# 16-ESP32S3.net
KiCad netlist of a schematic drawn in Altium Designer
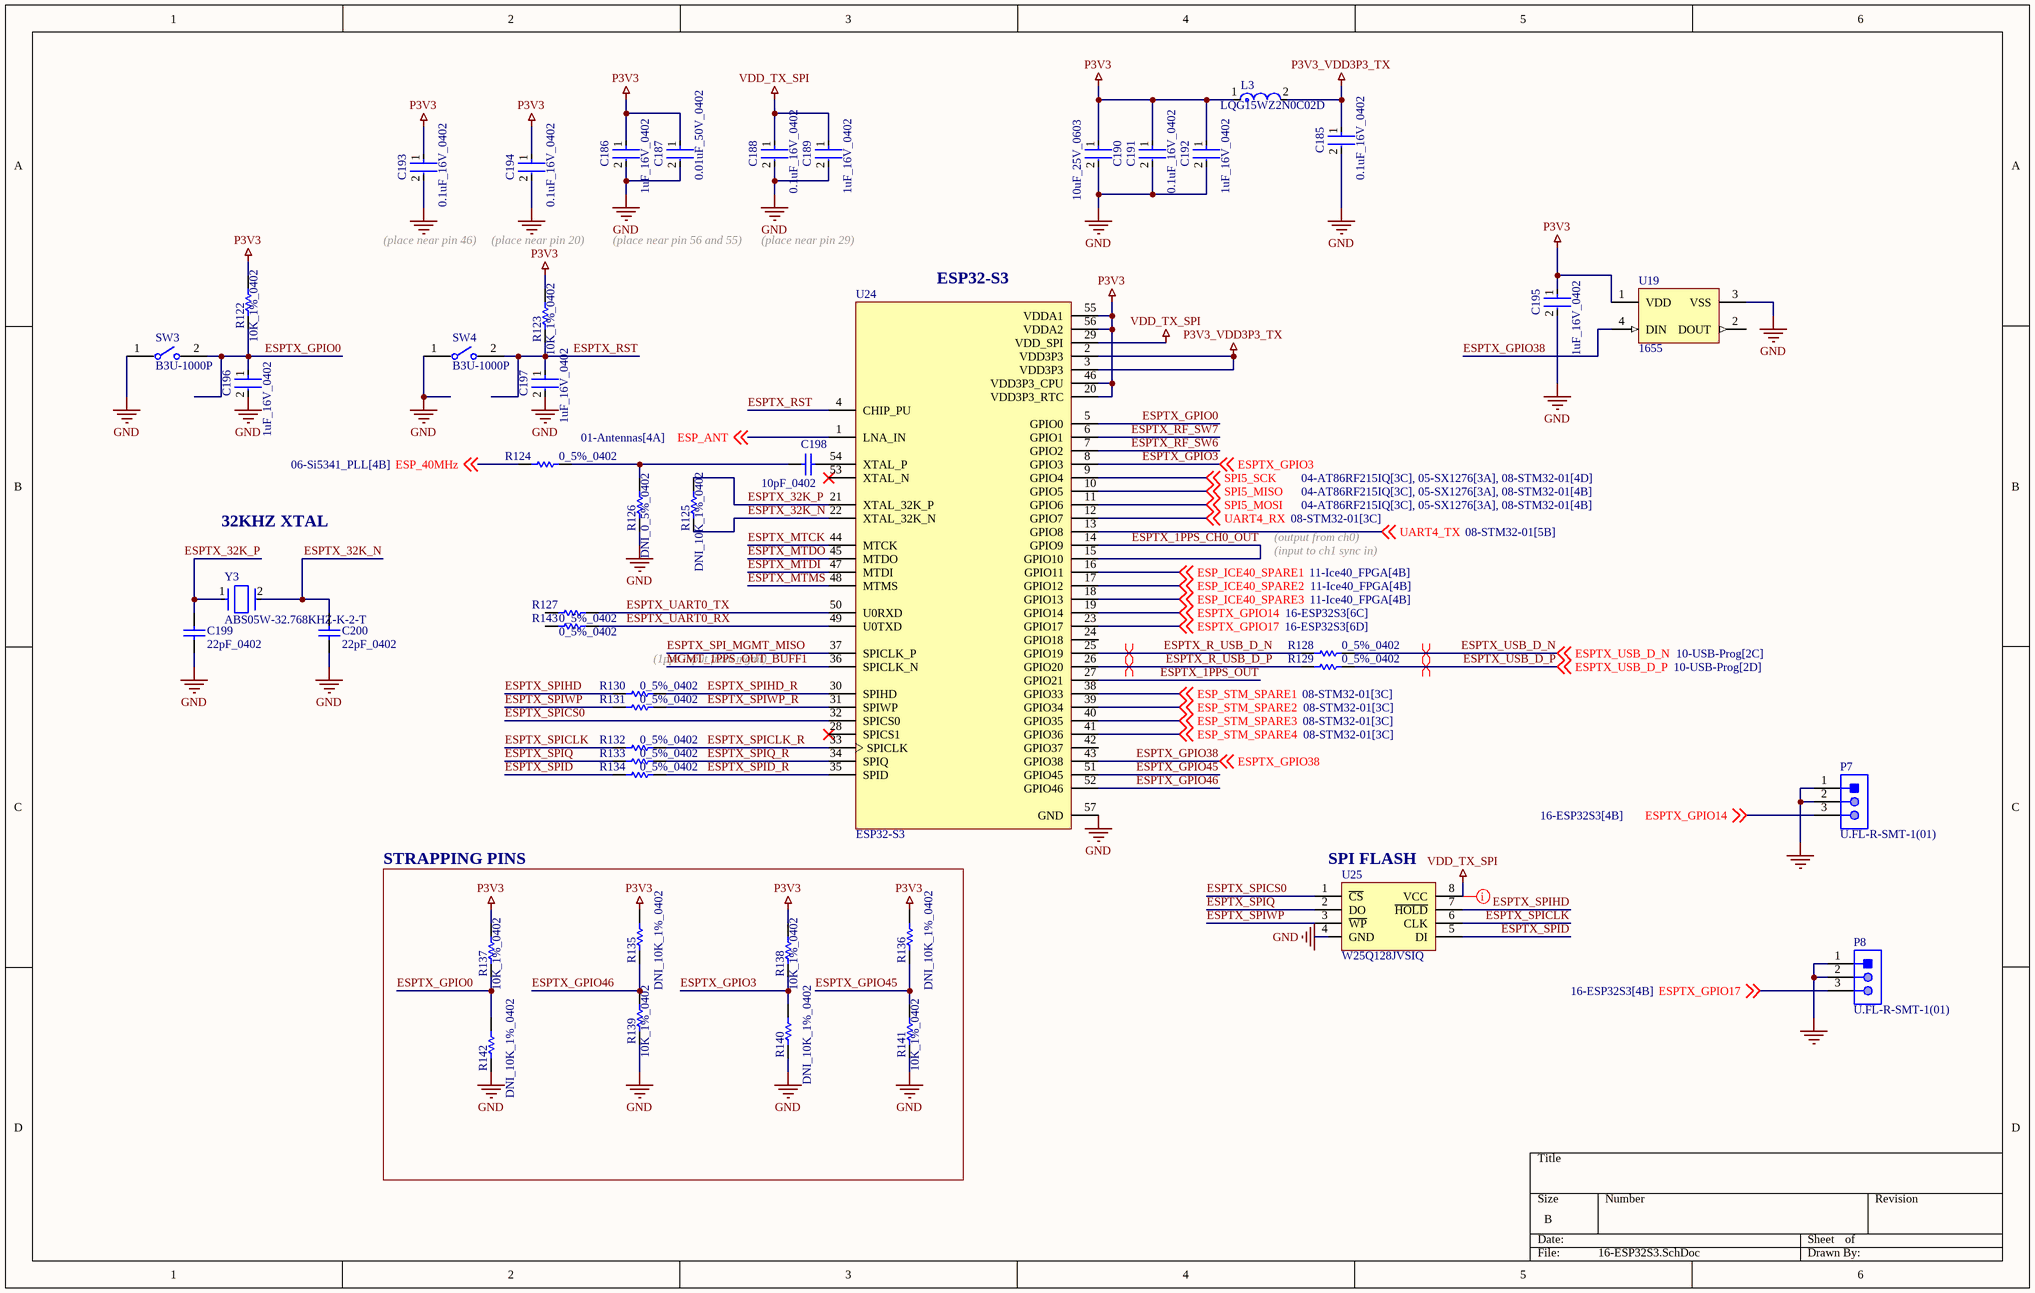
[diagram p0: 16-ESP32S3.SchDoc]

(export (version "E")
  (design (tool "Eeschema 10.0.6"))
  (components
    (comp (ref "C185")
      (value "0.1uF_16V_0402")
      (footprint "FP-C0402-BB-MFG")
      (description "CAP CER 0.1UF 16V 5% X7R 0402")
      (fields
        (field (name "MANUFACTURER") "Kemet")
        (field (name "MANUFACTURER PART NUMBER") "C0402C104J4RACTU")
      )
      (libsource (lib "Altium Content Vault") (part "b4654b650e69147ec39a6b967a45e02"))
    )
    (comp (ref "C186")
      (value "1uF_16V_0402")
      (footprint "FP-0402-L_1_0_0_05-W_0_5-IPC_A")
      (description "None")
      (fields (field (name "TOLERANCE") "10%"))
      (libsource (lib "Altium Content Vault") (part "b4654b650e69147ec39a6b967a45e02"))
    )
    (comp (ref "C187")
      (value "0.01uF_50V_0402")
      (footprint "FP-GCM155-0_05-IPC_C")
      (description "Ceramic Capacitor for Automotive 10nF ±10% 50VDC X7R 0402 Paper T/R")
      (fields (field (name "TOLERANCE") "10%") (field (name "VOLTAGE") "50V"))
      (libsource (lib "Altium Content Vault") (part "02cd4be3c70576c341d710602a673aa"))
    )
    (comp (ref "C188")
      (value "0.1uF_16V_0402")
      (footprint "FP-C0402-BB-MFG")
      (description "CAP CER 0.1UF 16V 5% X7R 0402")
      (fields
        (field (name "MANUFACTURER") "Kemet")
        (field (name "MANUFACTURER PART NUMBER") "C0402C104J4RACTU")
      )
      (libsource (lib "Altium Content Vault") (part "b4654b650e69147ec39a6b967a45e02"))
    )
    (comp (ref "C189")
      (value "1uF_16V_0402")
      (footprint "FP-0402-L_1_0_0_05-W_0_5-IPC_A")
      (description "None")
      (fields (field (name "TOLERANCE") "10%"))
      (libsource (lib "Altium Content Vault") (part "b4654b650e69147ec39a6b967a45e02"))
    )
    (comp (ref "C190")
      (value "10uF_25V_0603")
      (footprint "FP-CL10-IPC_C")
      (description "Cap Ceramic 10uF 25V X5R ±20% Pad SMD 0603 +85°C T/R")
      (fields (field (name "TOLERANCE") "20%"))
      (libsource (lib "Altium Content Vault") (part "b4654b650e69147ec39a6b967a45e02"))
    )
    (comp (ref "C191")
      (value "0.1uF_16V_0402")
      (footprint "FP-C0402-BB-MFG")
      (description "CAP CER 0.1UF 16V 5% X7R 0402")
      (fields
        (field (name "MANUFACTURER") "Kemet")
        (field (name "MANUFACTURER PART NUMBER") "C0402C104J4RACTU")
      )
      (libsource (lib "Altium Content Vault") (part "b4654b650e69147ec39a6b967a45e02"))
    )
    (comp (ref "C192")
      (value "1uF_16V_0402")
      (footprint "FP-0402-L_1_0_0_05-W_0_5-IPC_A")
      (description "None")
      (fields (field (name "TOLERANCE") "10%"))
      (libsource (lib "Altium Content Vault") (part "b4654b650e69147ec39a6b967a45e02"))
    )
    (comp (ref "C193")
      (value "0.1uF_16V_0402")
      (footprint "FP-C0402-BB-MFG")
      (description "CAP CER 0.1UF 16V 5% X7R 0402")
      (fields
        (field (name "MANUFACTURER") "Kemet")
        (field (name "MANUFACTURER PART NUMBER") "C0402C104J4RACTU")
      )
      (libsource (lib "Altium Content Vault") (part "b4654b650e69147ec39a6b967a45e02"))
    )
    (comp (ref "C194")
      (value "0.1uF_16V_0402")
      (footprint "FP-C0402-BB-MFG")
      (description "CAP CER 0.1UF 16V 5% X7R 0402")
      (fields
        (field (name "MANUFACTURER") "Kemet")
        (field (name "MANUFACTURER PART NUMBER") "C0402C104J4RACTU")
      )
      (libsource (lib "Altium Content Vault") (part "b4654b650e69147ec39a6b967a45e02"))
    )
    (comp (ref "C195")
      (value "1uF_16V_0402")
      (footprint "FP-0402-L_1_0_0_05-W_0_5-IPC_A")
      (description "None")
      (fields (field (name "TOLERANCE") "10%"))
      (libsource (lib "Altium Content Vault") (part "b4654b650e69147ec39a6b967a45e02"))
    )
    (comp (ref "C196")
      (value "1uF_16V_0402")
      (footprint "FP-0402-L_1_0_0_05-W_0_5-IPC_A")
      (description "None")
      (fields (field (name "TOLERANCE") "10%"))
      (libsource (lib "Altium Content Vault") (part "b4654b650e69147ec39a6b967a45e02"))
    )
    (comp (ref "C197")
      (value "1uF_16V_0402")
      (footprint "FP-0402-L_1_0_0_05-W_0_5-IPC_A")
      (description "None")
      (fields (field (name "TOLERANCE") "10%"))
      (libsource (lib "Altium Content Vault") (part "b4654b650e69147ec39a6b967a45e02"))
    )
    (comp (ref "C198")
      (value "10pF_0402")
      (footprint "CAPC1005X55X25ML05T05")
      (description "Chip Capacitor, 10 pF, +/- 5%, 50 V, -55 to 125 degC, 0402 (1005 Metric), RoHS, Tape and Reel")
      (fields (field (name "TOLERANCE") "5%") (field (name "MANUFACTURER") "Yageo"))
      (libsource (lib "Altium Content Vault") (part "CAP-NP-2"))
    )
    (comp (ref "C199")
      (value "22pF_0402")
      (footprint "CAPC1005X55X25ML05T05")
      (description "Chip Capacitor, 22 pF, +/- 5%, 50 V, -55 to 125 degC, 0402 (1005 Metric), RoHS, Tape and Reel")
      (fields (field (name "MANUFACTURER") "Yageo") (field (name "TOLERANCE") "5%"))
      (libsource (lib "Altium Content Vault") (part "CAP-NP-2"))
    )
    (comp (ref "C200")
      (value "22pF_0402")
      (footprint "CAPC1005X55X25ML05T05")
      (description "Chip Capacitor, 22 pF, +/- 5%, 50 V, -55 to 125 degC, 0402 (1005 Metric), RoHS, Tape and Reel")
      (fields (field (name "MANUFACTURER") "Yageo") (field (name "TOLERANCE") "5%"))
      (libsource (lib "Altium Content Vault") (part "CAP-NP-2"))
    )
    (comp (ref "L3")
      (value "LQG15WZ2N0C02D")
      (footprint "FP-LQG15WH_02-IPC_B")
      (description "Multilayer type Inductor for Automotive 2nH ±0.2nH 0.05Ω 1000mA 0402")
      (libsource (lib "Altium Content Vault") (part "4cc4b267dca4c8e51f7102f422741d8"))
    )
    (comp (ref "P7")
      (value "U.FL-R-SMT-1(01)")
      (footprint "HRS-U.FL-R-SMT-3_V")
      (description "Ultra Small Coaxial Connector, 6 GHz, -40 to 90 degC, 3-Pin SMD, RoHS, Bulk")
      (fields (field (name "MANUFACTURER") "Hirose Electric"))
      (libsource (lib "Altium Content Vault") (part "CN-1P-M-R3"))
    )
    (comp (ref "P8")
      (value "U.FL-R-SMT-1(01)")
      (footprint "HRS-U.FL-R-SMT-3_V")
      (description "Ultra Small Coaxial Connector, 6 GHz, -40 to 90 degC, 3-Pin SMD, RoHS, Bulk")
      (fields (field (name "MANUFACTURER") "Hirose Electric"))
      (libsource (lib "Altium Content Vault") (part "CN-1P-M-R3"))
    )
    (comp (ref "R122")
      (value "10K_1%_0402")
      (footprint "RESC1005X40X25NL10T10")
      (fields (field (name "MANUFACTURER") "Bourns") (field (name "PART NUMBER") "CR0402-FX-1002GLF"))
      (libsource (lib "Altium Content Vault") (part "RES"))
    )
    (comp (ref "R123")
      (value "10K_1%_0402")
      (footprint "RESC1005X40X25NL10T10")
      (fields (field (name "MANUFACTURER") "Bourns") (field (name "PART NUMBER") "CR0402-FX-1002GLF"))
      (libsource (lib "Altium Content Vault") (part "RES"))
    )
    (comp (ref "R124")
      (value "0_5%_0402")
      (footprint "RESC1005X40X25NL05T10")
      (fields (field (name "MANUFACTURER") "Panasonic") (field (name "PART NUMBER") "ERJ-U020R00X"))
      (libsource (lib "Altium Content Vault") (part "RES"))
    )
    (comp (ref "R125")
      (value "DNI_10K_1%_0402")
      (footprint "RESC1005X40X25NL10T10")
      (fields (field (name "MANUFACTURER") "Bourns") (field (name "PART NUMBER") "CR0402-FX-1002GLF"))
      (libsource (lib "Altium Content Vault") (part "RES"))
    )
    (comp (ref "R126")
      (value "DNI_0_5%_0402")
      (footprint "RESC1005X40X25NL05T10")
      (fields (field (name "MANUFACTURER") "Panasonic") (field (name "PART NUMBER") "ERJ-U020R00X"))
      (libsource (lib "Altium Content Vault") (part "RES"))
    )
    (comp (ref "R127")
      (value "0_5%_0402")
      (footprint "RESC1005X40X25NL05T10")
      (fields (field (name "MANUFACTURER") "Panasonic") (field (name "PART NUMBER") "ERJ-U020R00X"))
      (libsource (lib "Altium Content Vault") (part "RES"))
    )
    (comp (ref "R128")
      (value "0_5%_0402")
      (footprint "RESC1005X40X25NL05T10")
      (fields (field (name "MANUFACTURER") "Panasonic") (field (name "PART NUMBER") "ERJ-U020R00X"))
      (libsource (lib "Altium Content Vault") (part "RES"))
    )
    (comp (ref "R129")
      (value "0_5%_0402")
      (footprint "RESC1005X40X25NL05T10")
      (fields (field (name "MANUFACTURER") "Panasonic") (field (name "PART NUMBER") "ERJ-U020R00X"))
      (libsource (lib "Altium Content Vault") (part "RES"))
    )
    (comp (ref "R130")
      (value "0_5%_0402")
      (footprint "RESC1005X40X25NL05T10")
      (fields (field (name "MANUFACTURER") "Panasonic") (field (name "PART NUMBER") "ERJ-U020R00X"))
      (libsource (lib "Altium Content Vault") (part "RES"))
    )
    (comp (ref "R131")
      (value "0_5%_0402")
      (footprint "RESC1005X40X25NL05T10")
      (fields (field (name "MANUFACTURER") "Panasonic") (field (name "PART NUMBER") "ERJ-U020R00X"))
      (libsource (lib "Altium Content Vault") (part "RES"))
    )
    (comp (ref "R132")
      (value "0_5%_0402")
      (footprint "RESC1005X40X25NL05T10")
      (fields (field (name "MANUFACTURER") "Panasonic") (field (name "PART NUMBER") "ERJ-U020R00X"))
      (libsource (lib "Altium Content Vault") (part "RES"))
    )
    (comp (ref "R133")
      (value "0_5%_0402")
      (footprint "RESC1005X40X25NL05T10")
      (fields (field (name "MANUFACTURER") "Panasonic") (field (name "PART NUMBER") "ERJ-U020R00X"))
      (libsource (lib "Altium Content Vault") (part "RES"))
    )
    (comp (ref "R134")
      (value "0_5%_0402")
      (footprint "RESC1005X40X25NL05T10")
      (fields (field (name "MANUFACTURER") "Panasonic") (field (name "PART NUMBER") "ERJ-U020R00X"))
      (libsource (lib "Altium Content Vault") (part "RES"))
    )
    (comp (ref "R135")
      (value "DNI_10K_1%_0402")
      (footprint "RESC1005X40X25NL10T10")
      (fields (field (name "MANUFACTURER") "Bourns") (field (name "PART NUMBER") "CR0402-FX-1002GLF"))
      (libsource (lib "Altium Content Vault") (part "RES"))
    )
    (comp (ref "R136")
      (value "DNI_10K_1%_0402")
      (footprint "RESC1005X40X25NL10T10")
      (fields (field (name "MANUFACTURER") "Bourns") (field (name "PART NUMBER") "CR0402-FX-1002GLF"))
      (libsource (lib "Altium Content Vault") (part "RES"))
    )
    (comp (ref "R137")
      (value "10K_1%_0402")
      (footprint "RESC1005X40X25NL10T10")
      (fields (field (name "MANUFACTURER") "Bourns") (field (name "PART NUMBER") "CR0402-FX-1002GLF"))
      (libsource (lib "Altium Content Vault") (part "RES"))
    )
    (comp (ref "R138")
      (value "10K_1%_0402")
      (footprint "RESC1005X40X25NL10T10")
      (fields (field (name "MANUFACTURER") "Bourns") (field (name "PART NUMBER") "CR0402-FX-1002GLF"))
      (libsource (lib "Altium Content Vault") (part "RES"))
    )
    (comp (ref "R139")
      (value "10K_1%_0402")
      (footprint "RESC1005X40X25NL10T10")
      (fields (field (name "MANUFACTURER") "Bourns") (field (name "PART NUMBER") "CR0402-FX-1002GLF"))
      (libsource (lib "Altium Content Vault") (part "RES"))
    )
    (comp (ref "R140")
      (value "DNI_10K_1%_0402")
      (footprint "RESC1005X40X25NL10T10")
      (fields (field (name "MANUFACTURER") "Bourns") (field (name "PART NUMBER") "CR0402-FX-1002GLF"))
      (libsource (lib "Altium Content Vault") (part "RES"))
    )
    (comp (ref "R141")
      (value "10K_1%_0402")
      (footprint "RESC1005X40X25NL10T10")
      (fields (field (name "MANUFACTURER") "Bourns") (field (name "PART NUMBER") "CR0402-FX-1002GLF"))
      (libsource (lib "Altium Content Vault") (part "RES"))
    )
    (comp (ref "R142")
      (value "DNI_10K_1%_0402")
      (footprint "RESC1005X40X25NL10T10")
      (fields (field (name "MANUFACTURER") "Bourns") (field (name "PART NUMBER") "CR0402-FX-1002GLF"))
      (libsource (lib "Altium Content Vault") (part "RES"))
    )
    (comp (ref "R143")
      (value "0_5%_0402")
      (footprint "RESC1005X40X25NL05T10")
      (fields (field (name "MANUFACTURER") "Panasonic") (field (name "PART NUMBER") "ERJ-U020R00X"))
      (libsource (lib "Altium Content Vault") (part "RES"))
    )
    (comp (ref "SW3")
      (value "B3U-1000P")
      (footprint "FP-B3U-1000P-MFG")
      (description "SWITCH TACTILE SPST-NO 0.05A 12V")
      (libsource (lib "Altium Content Vault") (part "ae622034201233ca1abcedc05908f33"))
    )
    (comp (ref "SW4")
      (value "B3U-1000P")
      (footprint "FP-B3U-1000P-MFG")
      (description "SWITCH TACTILE SPST-NO 0.05A 12V")
      (libsource (lib "Altium Content Vault") (part "ae622034201233ca1abcedc05908f33"))
    )
    (comp (ref "U19")
      (value "1655")
      (footprint "ADA-RGB-1655_V")
      (fields (field (name "MANUFACTURER") "Adafruit-Industries-LLC"))
      (libsource (lib "Altium Content Vault") (part "ADA-RGB-1655-4"))
    )
    (comp (ref "U24")
      (value "ESP32-S3")
      (footprint "IC_ESP32-S3")
      (fields (field (name "MF") "Espressif Systems"))
      (libsource (lib "LotusSound") (part "IC_ESP32-S3"))
    )
    (comp (ref "U25")
      (value "W25Q128JVSIQ")
      (footprint "IC_W25Q128JVSIQ")
      (description "NOR Flash Serial (SPI, Dual SPI, Quad SPI) 3.3V 128M-bit 16M x 8 6ns 8-Pin SOIC Tube")
      (fields (field (name "MANUFACTURER") "Winbond"))
      (libsource (lib "LotusSound") (part "IC_W25Q128JVSIQ"))
    )
    (comp (ref "Y3")
      (value "ABS05W-32.768KHZ-K-2-T")
      (footprint "FP-ABS05W-MFG")
      (description "Crystal 32.768kHz ±20ppm (Tol) 4pF 85kΩ 2-Pin SMD T/R")
      (libsource (lib "Altium Content Vault") (part "c23a69dc6c9e2f18f2079038eb95dd1"))
    )
  )
  (nets
    (net (code "1") (name "/ESPTX_1PPS_CH0_OUT") (class "Default")
      (node (ref "U24") (pin "14") (pinfunction "GPIO9_14") (pintype "passive"))
      (node (ref "U24") (pin "15") (pinfunction "GPIO10_15") (pintype "passive"))
    )
    (net (code "2") (name "/ESPTX_1PPS_OUT") (class "Default")
      (node (ref "U24") (pin "27") (pinfunction "GPIO21_27") (pintype "passive"))
    )
    (net (code "3") (name "/ESPTX_32K_N") (class "Default")
      (node (ref "C200") (pin "2") (pinfunction "2_2") (pintype "passive"))
      (node (ref "R125") (pin "1") (pinfunction "1_1") (pintype "passive"))
      (node (ref "U24") (pin "22") (pinfunction "XTAL_32K_N_22") (pintype "passive"))
      (node (ref "Y3") (pin "2") (pinfunction "2_2") (pintype "passive"))
    )
    (net (code "4") (name "/ESPTX_32K_P") (class "Default")
      (node (ref "C199") (pin "2") (pinfunction "2_2") (pintype "passive"))
      (node (ref "R125") (pin "2") (pinfunction "2_2") (pintype "passive"))
      (node (ref "U24") (pin "21") (pinfunction "XTAL_32K_P_21") (pintype "passive"))
      (node (ref "Y3") (pin "1") (pinfunction "1_1") (pintype "passive"))
    )
    (net (code "5") (name "/ESPTX_GPIO0") (class "Default")
      (node (ref "C196") (pin "1") (pinfunction "1_1") (pintype "passive"))
      (node (ref "R122") (pin "1") (pinfunction "1_1") (pintype "passive"))
      (node (ref "R137") (pin "1") (pinfunction "1_1") (pintype "passive"))
      (node (ref "R142") (pin "2") (pinfunction "2_2") (pintype "passive"))
      (node (ref "SW3") (pin "2") (pinfunction "2_2") (pintype "passive"))
      (node (ref "U24") (pin "5") (pinfunction "GPIO0_5") (pintype "passive"))
    )
    (net (code "6") (name "/ESPTX_GPIO45") (class "Default")
      (node (ref "R136") (pin "1") (pinfunction "1_1") (pintype "passive"))
      (node (ref "R141") (pin "2") (pinfunction "2_2") (pintype "passive"))
      (node (ref "U24") (pin "51") (pinfunction "GPIO45_51") (pintype "passive"))
    )
    (net (code "7") (name "/ESPTX_GPIO46") (class "Default")
      (node (ref "R135") (pin "1") (pinfunction "1_1") (pintype "passive"))
      (node (ref "R139") (pin "2") (pinfunction "2_2") (pintype "passive"))
      (node (ref "U24") (pin "52") (pinfunction "GPIO46_52") (pintype "passive"))
    )
    (net (code "8") (name "/ESPTX_MTCK") (class "Default")
      (node (ref "U24") (pin "44") (pinfunction "MTCK_44") (pintype "passive"))
    )
    (net (code "9") (name "/ESPTX_MTDI") (class "Default")
      (node (ref "U24") (pin "47") (pinfunction "MTDI_47") (pintype "passive"))
    )
    (net (code "10") (name "/ESPTX_MTDO") (class "Default")
      (node (ref "U24") (pin "45") (pinfunction "MTDO_45") (pintype "passive"))
    )
    (net (code "11") (name "/ESPTX_MTMS") (class "Default")
      (node (ref "U24") (pin "48") (pinfunction "MTMS_48") (pintype "passive"))
    )
    (net (code "12") (name "/ESPTX_RF_SW6") (class "Default")
      (node (ref "U24") (pin "7") (pinfunction "GPIO2_7") (pintype "passive"))
    )
    (net (code "13") (name "/ESPTX_RF_SW7") (class "Default")
      (node (ref "U24") (pin "6") (pinfunction "GPIO1_6") (pintype "passive"))
    )
    (net (code "14") (name "/ESPTX_RST") (class "Default")
      (node (ref "C197") (pin "1") (pinfunction "1_1") (pintype "passive"))
      (node (ref "R123") (pin "1") (pinfunction "1_1") (pintype "passive"))
      (node (ref "SW4") (pin "2") (pinfunction "2_2") (pintype "passive"))
      (node (ref "U24") (pin "4") (pinfunction "CHIP_PU_4") (pintype "passive"))
    )
    (net (code "15") (name "/ESPTX_R_USB_D_N") (class "Default")
      (node (ref "R128") (pin "1") (pinfunction "1_1") (pintype "passive"))
      (node (ref "U24") (pin "25") (pinfunction "GPIO19_25") (pintype "passive"))
    )
    (net (code "16") (name "/ESPTX_R_USB_D_P") (class "Default")
      (node (ref "R129") (pin "1") (pinfunction "1_1") (pintype "passive"))
      (node (ref "U24") (pin "26") (pinfunction "GPIO20_26") (pintype "passive"))
    )
    (net (code "17") (name "/ESPTX_SPICLK") (class "Default")
      (node (ref "R132") (pin "1") (pinfunction "1_1") (pintype "passive"))
      (node (ref "U25") (pin "6") (pinfunction "CLK_6") (pintype "passive"))
    )
    (net (code "18") (name "/ESPTX_SPICLK_R") (class "Default")
      (node (ref "R132") (pin "2") (pinfunction "2_2") (pintype "passive"))
      (node (ref "U24") (pin "33") (pinfunction "SPICLK_33") (pintype "passive"))
    )
    (net (code "19") (name "/ESPTX_SPICS0") (class "Default")
      (node (ref "U24") (pin "32") (pinfunction "SPICS0_32") (pintype "passive"))
      (node (ref "U25") (pin "1") (pinfunction "~{CS}_1") (pintype "passive"))
    )
    (net (code "20") (name "/ESPTX_SPID") (class "Default")
      (node (ref "R134") (pin "1") (pinfunction "1_1") (pintype "passive"))
      (node (ref "U25") (pin "5") (pinfunction "DI_5") (pintype "passive"))
    )
    (net (code "21") (name "/ESPTX_SPID_R") (class "Default")
      (node (ref "R134") (pin "2") (pinfunction "2_2") (pintype "passive"))
      (node (ref "U24") (pin "35") (pinfunction "SPID_35") (pintype "passive"))
    )
    (net (code "22") (name "/ESPTX_SPIHD") (class "Default")
      (node (ref "R130") (pin "1") (pinfunction "1_1") (pintype "passive"))
      (node (ref "U25") (pin "7") (pinfunction "~{HOLD}_7") (pintype "passive"))
    )
    (net (code "23") (name "/ESPTX_SPIHD_R") (class "Default")
      (node (ref "R130") (pin "2") (pinfunction "2_2") (pintype "passive"))
      (node (ref "U24") (pin "30") (pinfunction "SPIHD_30") (pintype "passive"))
    )
    (net (code "24") (name "/ESPTX_SPIQ") (class "Default")
      (node (ref "R133") (pin "1") (pinfunction "1_1") (pintype "passive"))
      (node (ref "U25") (pin "2") (pinfunction "DO_2") (pintype "passive"))
    )
    (net (code "25") (name "/ESPTX_SPIQ_R") (class "Default")
      (node (ref "R133") (pin "2") (pinfunction "2_2") (pintype "passive"))
      (node (ref "U24") (pin "34") (pinfunction "SPIQ_34") (pintype "passive"))
    )
    (net (code "26") (name "/ESPTX_SPIWP") (class "Default")
      (node (ref "R131") (pin "1") (pinfunction "1_1") (pintype "passive"))
      (node (ref "U25") (pin "3") (pinfunction "~{WP}_3") (pintype "passive"))
    )
    (net (code "27") (name "/ESPTX_SPIWP_R") (class "Default")
      (node (ref "R131") (pin "2") (pinfunction "2_2") (pintype "passive"))
      (node (ref "U24") (pin "31") (pinfunction "SPIWP_31") (pintype "passive"))
    )
    (net (code "28") (name "/ESPTX_SPI_MGMT_MISO") (class "Default")
      (node (ref "U24") (pin "37") (pinfunction "SPICLK_P_37") (pintype "passive"))
    )
    (net (code "29") (name "/ESPTX_UART0_RX") (class "Default")
      (node (ref "R143") (pin "2") (pinfunction "2_2") (pintype "passive"))
      (node (ref "U24") (pin "49") (pinfunction "U0TXD_49") (pintype "passive"))
    )
    (net (code "30") (name "/ESPTX_UART0_TX") (class "Default")
      (node (ref "R127") (pin "2") (pinfunction "2_2") (pintype "passive"))
      (node (ref "U24") (pin "50") (pinfunction "U0RXD_50") (pintype "passive"))
    )
    (net (code "31") (name "/MGMT_1PPS_OUT_BUFF1") (class "Default")
      (node (ref "U24") (pin "36") (pinfunction "SPICLK_N_36") (pintype "passive"))
    )
    (net (code "32") (name "ESPTX_GPIO3") (class "Default")
      (node (ref "R138") (pin "1") (pinfunction "1_1") (pintype "passive"))
      (node (ref "R140") (pin "2") (pinfunction "2_2") (pintype "passive"))
      (node (ref "U24") (pin "8") (pinfunction "GPIO3_8") (pintype "passive"))
    )
    (net (code "33") (name "ESPTX_GPIO14") (class "Default")
      (node (ref "P7") (pin "3") (pinfunction "3_3") (pintype "passive"))
      (node (ref "U24") (pin "19") (pinfunction "GPIO14_19") (pintype "passive"))
    )
    (net (code "34") (name "ESPTX_GPIO17") (class "Default")
      (node (ref "P8") (pin "3") (pinfunction "3_3") (pintype "passive"))
      (node (ref "U24") (pin "23") (pinfunction "GPIO17_23") (pintype "passive"))
    )
    (net (code "35") (name "ESPTX_GPIO38") (class "Default")
      (node (ref "U19") (pin "4") (pinfunction "DIN_4") (pintype "input"))
      (node (ref "U24") (pin "43") (pinfunction "GPIO38_43") (pintype "passive"))
    )
    (net (code "36") (name "ESPTX_USB_D_N") (class "Default")
      (node (ref "R128") (pin "2") (pinfunction "2_2") (pintype "passive"))
    )
    (net (code "37") (name "ESPTX_USB_D_P") (class "Default")
      (node (ref "R129") (pin "2") (pinfunction "2_2") (pintype "passive"))
    )
    (net (code "38") (name "ESP_40MHz") (class "Default")
      (node (ref "R124") (pin "1") (pinfunction "1_1") (pintype "passive"))
    )
    (net (code "39") (name "ESP_ANT") (class "Default")
      (node (ref "U24") (pin "1") (pinfunction "LNA_IN_1") (pintype "passive"))
    )
    (net (code "40") (name "ESP_ICE40_SPARE1") (class "Default")
      (node (ref "U24") (pin "16") (pinfunction "GPIO11_16") (pintype "passive"))
    )
    (net (code "41") (name "ESP_ICE40_SPARE2") (class "Default")
      (node (ref "U24") (pin "17") (pinfunction "GPIO12_17") (pintype "passive"))
    )
    (net (code "42") (name "ESP_ICE40_SPARE3") (class "Default")
      (node (ref "U24") (pin "18") (pinfunction "GPIO13_18") (pintype "passive"))
    )
    (net (code "43") (name "ESP_STM_SPARE1") (class "Default")
      (node (ref "U24") (pin "38") (pinfunction "GPIO33_38") (pintype "passive"))
    )
    (net (code "44") (name "ESP_STM_SPARE2") (class "Default")
      (node (ref "U24") (pin "39") (pinfunction "GPIO34_39") (pintype "passive"))
    )
    (net (code "45") (name "ESP_STM_SPARE3") (class "Default")
      (node (ref "U24") (pin "40") (pinfunction "GPIO35_40") (pintype "passive"))
    )
    (net (code "46") (name "ESP_STM_SPARE4") (class "Default")
      (node (ref "U24") (pin "41") (pinfunction "GPIO36_41") (pintype "passive"))
    )
    (net (code "47") (name "GND") (class "Default")
      (node (ref "C185") (pin "2") (pinfunction "2_2") (pintype "passive"))
      (node (ref "C186") (pin "2") (pinfunction "2_2") (pintype "passive"))
      (node (ref "C187") (pin "2") (pinfunction "2_2") (pintype "passive"))
      (node (ref "C188") (pin "2") (pinfunction "2_2") (pintype "passive"))
      (node (ref "C189") (pin "2") (pinfunction "2_2") (pintype "passive"))
      (node (ref "C190") (pin "2") (pinfunction "2_2") (pintype "passive"))
      (node (ref "C191") (pin "2") (pinfunction "2_2") (pintype "passive"))
      (node (ref "C192") (pin "2") (pinfunction "2_2") (pintype "passive"))
      (node (ref "C193") (pin "2") (pinfunction "2_2") (pintype "passive"))
      (node (ref "C194") (pin "2") (pinfunction "2_2") (pintype "passive"))
      (node (ref "C195") (pin "2") (pinfunction "2_2") (pintype "passive"))
      (node (ref "C196") (pin "2") (pinfunction "2_2") (pintype "passive"))
      (node (ref "C197") (pin "2") (pinfunction "2_2") (pintype "passive"))
      (node (ref "C199") (pin "1") (pinfunction "1_1") (pintype "passive"))
      (node (ref "C200") (pin "1") (pinfunction "1_1") (pintype "passive"))
      (node (ref "P7") (pin "1") (pinfunction "1_1") (pintype "passive"))
      (node (ref "P7") (pin "2") (pinfunction "2_2") (pintype "passive"))
      (node (ref "P8") (pin "1") (pinfunction "1_1") (pintype "passive"))
      (node (ref "P8") (pin "2") (pinfunction "2_2") (pintype "passive"))
      (node (ref "R126") (pin "1") (pinfunction "1_1") (pintype "passive"))
      (node (ref "R139") (pin "1") (pinfunction "1_1") (pintype "passive"))
      (node (ref "R140") (pin "1") (pinfunction "1_1") (pintype "passive"))
      (node (ref "R141") (pin "1") (pinfunction "1_1") (pintype "passive"))
      (node (ref "R142") (pin "1") (pinfunction "1_1") (pintype "passive"))
      (node (ref "SW3") (pin "1") (pinfunction "1_1") (pintype "passive"))
      (node (ref "SW4") (pin "1") (pinfunction "1_1") (pintype "passive"))
      (node (ref "U19") (pin "3") (pinfunction "VSS_3") (pintype "power_in"))
      (node (ref "U24") (pin "57") (pinfunction "GND_57") (pintype "passive"))
      (node (ref "U25") (pin "4") (pinfunction "GND_4") (pintype "power_in"))
    )
    (net (code "48") (name "Net-(C198-Pad1)") (class "Default")
      (node (ref "C198") (pin "1") (pinfunction "1_1") (pintype "passive"))
      (node (ref "R124") (pin "2") (pinfunction "2_2") (pintype "passive"))
      (node (ref "R126") (pin "2") (pinfunction "2_2") (pintype "passive"))
    )
    (net (code "49") (name "Net-(U24-XTAL_P)") (class "Default")
      (node (ref "C198") (pin "2") (pinfunction "2_2") (pintype "passive"))
      (node (ref "U24") (pin "54") (pinfunction "XTAL_P_54") (pintype "passive"))
    )
    (net (code "50") (name "P3V3") (class "Default")
      (node (ref "C186") (pin "1") (pinfunction "1_1") (pintype "passive"))
      (node (ref "C187") (pin "1") (pinfunction "1_1") (pintype "passive"))
      (node (ref "C190") (pin "1") (pinfunction "1_1") (pintype "passive"))
      (node (ref "C191") (pin "1") (pinfunction "1_1") (pintype "passive"))
      (node (ref "C192") (pin "1") (pinfunction "1_1") (pintype "passive"))
      (node (ref "C193") (pin "1") (pinfunction "1_1") (pintype "passive"))
      (node (ref "C194") (pin "1") (pinfunction "1_1") (pintype "passive"))
      (node (ref "C195") (pin "1") (pinfunction "1_1") (pintype "passive"))
      (node (ref "L3") (pin "1") (pinfunction "1_1") (pintype "passive"))
      (node (ref "R122") (pin "2") (pinfunction "2_2") (pintype "passive"))
      (node (ref "R123") (pin "2") (pinfunction "2_2") (pintype "passive"))
      (node (ref "R135") (pin "2") (pinfunction "2_2") (pintype "passive"))
      (node (ref "R136") (pin "2") (pinfunction "2_2") (pintype "passive"))
      (node (ref "R137") (pin "2") (pinfunction "2_2") (pintype "passive"))
      (node (ref "R138") (pin "2") (pinfunction "2_2") (pintype "passive"))
      (node (ref "U19") (pin "1") (pinfunction "VDD_1") (pintype "power_in"))
      (node (ref "U24") (pin "20") (pinfunction "VDD3P3_RTC_20") (pintype "passive"))
      (node (ref "U24") (pin "46") (pinfunction "VDD3P3_CPU_46") (pintype "passive"))
      (node (ref "U24") (pin "55") (pinfunction "VDDA1_55") (pintype "power_in"))
      (node (ref "U24") (pin "56") (pinfunction "VDDA2_56") (pintype "passive"))
    )
    (net (code "51") (name "P3V3_VDD3P3_TX") (class "Default")
      (node (ref "C185") (pin "1") (pinfunction "1_1") (pintype "passive"))
      (node (ref "L3") (pin "2") (pinfunction "2_2") (pintype "passive"))
      (node (ref "U24") (pin "2") (pinfunction "VDD3P3_2") (pintype "passive"))
      (node (ref "U24") (pin "3") (pinfunction "VDD3P3_3") (pintype "passive"))
    )
    (net (code "52") (name "SPI5_MISO") (class "Default")
      (node (ref "U24") (pin "10") (pinfunction "GPIO5_10") (pintype "passive"))
    )
    (net (code "53") (name "SPI5_MOSI") (class "Default")
      (node (ref "U24") (pin "11") (pinfunction "GPIO6_11") (pintype "passive"))
    )
    (net (code "54") (name "SPI5_SCK") (class "Default")
      (node (ref "U24") (pin "9") (pinfunction "GPIO4_9") (pintype "passive"))
    )
    (net (code "55") (name "UART4_RX") (class "Default")
      (node (ref "U24") (pin "12") (pinfunction "GPIO7_12") (pintype "passive"))
    )
    (net (code "56") (name "UART4_TX") (class "Default")
      (node (ref "U24") (pin "13") (pinfunction "GPIO8_13") (pintype "passive"))
    )
    (net (code "57") (name "VDD_TX_SPI") (class "Default")
      (node (ref "C188") (pin "1") (pinfunction "1_1") (pintype "passive"))
      (node (ref "C189") (pin "1") (pinfunction "1_1") (pintype "passive"))
      (node (ref "U24") (pin "29") (pinfunction "VDD_SPI_29") (pintype "passive"))
      (node (ref "U25") (pin "8") (pinfunction "VCC_8") (pintype "passive"))
    )
    (net (code "58") (name "unconnected-(R127-Pad1)") (class "Default")
      (node (ref "R127") (pin "1") (pinfunction "1_1") (pintype "passive"))
    )
    (net (code "59") (name "unconnected-(R143-Pad1)") (class "Default")
      (node (ref "R143") (pin "1") (pinfunction "1_1") (pintype "passive"))
    )
    (net (code "60") (name "unconnected-(U19-DOUT-Pad2)") (class "Default")
      (node (ref "U19") (pin "2") (pinfunction "DOUT_2") (pintype "output"))
    )
    (net (code "61") (name "unconnected-(U24-GPIO18-Pad24)") (class "Default")
      (node (ref "U24") (pin "24") (pinfunction "GPIO18_24") (pintype "passive"))
    )
    (net (code "62") (name "unconnected-(U24-GPIO37-Pad42)") (class "Default")
      (node (ref "U24") (pin "42") (pinfunction "GPIO37_42") (pintype "passive"))
    )
    (net (code "63") (name "unconnected-(U24-SPICS1-Pad28)") (class "Default")
      (node (ref "U24") (pin "28") (pinfunction "SPICS1_28") (pintype "passive+no_connect"))
    )
    (net (code "64") (name "unconnected-(U24-XTAL_N-Pad53)") (class "Default")
      (node (ref "U24") (pin "53") (pinfunction "XTAL_N_53") (pintype "passive+no_connect"))
    )
  )
)
